# charger.net
KiCad netlist of a schematic drawn in Altium Designer
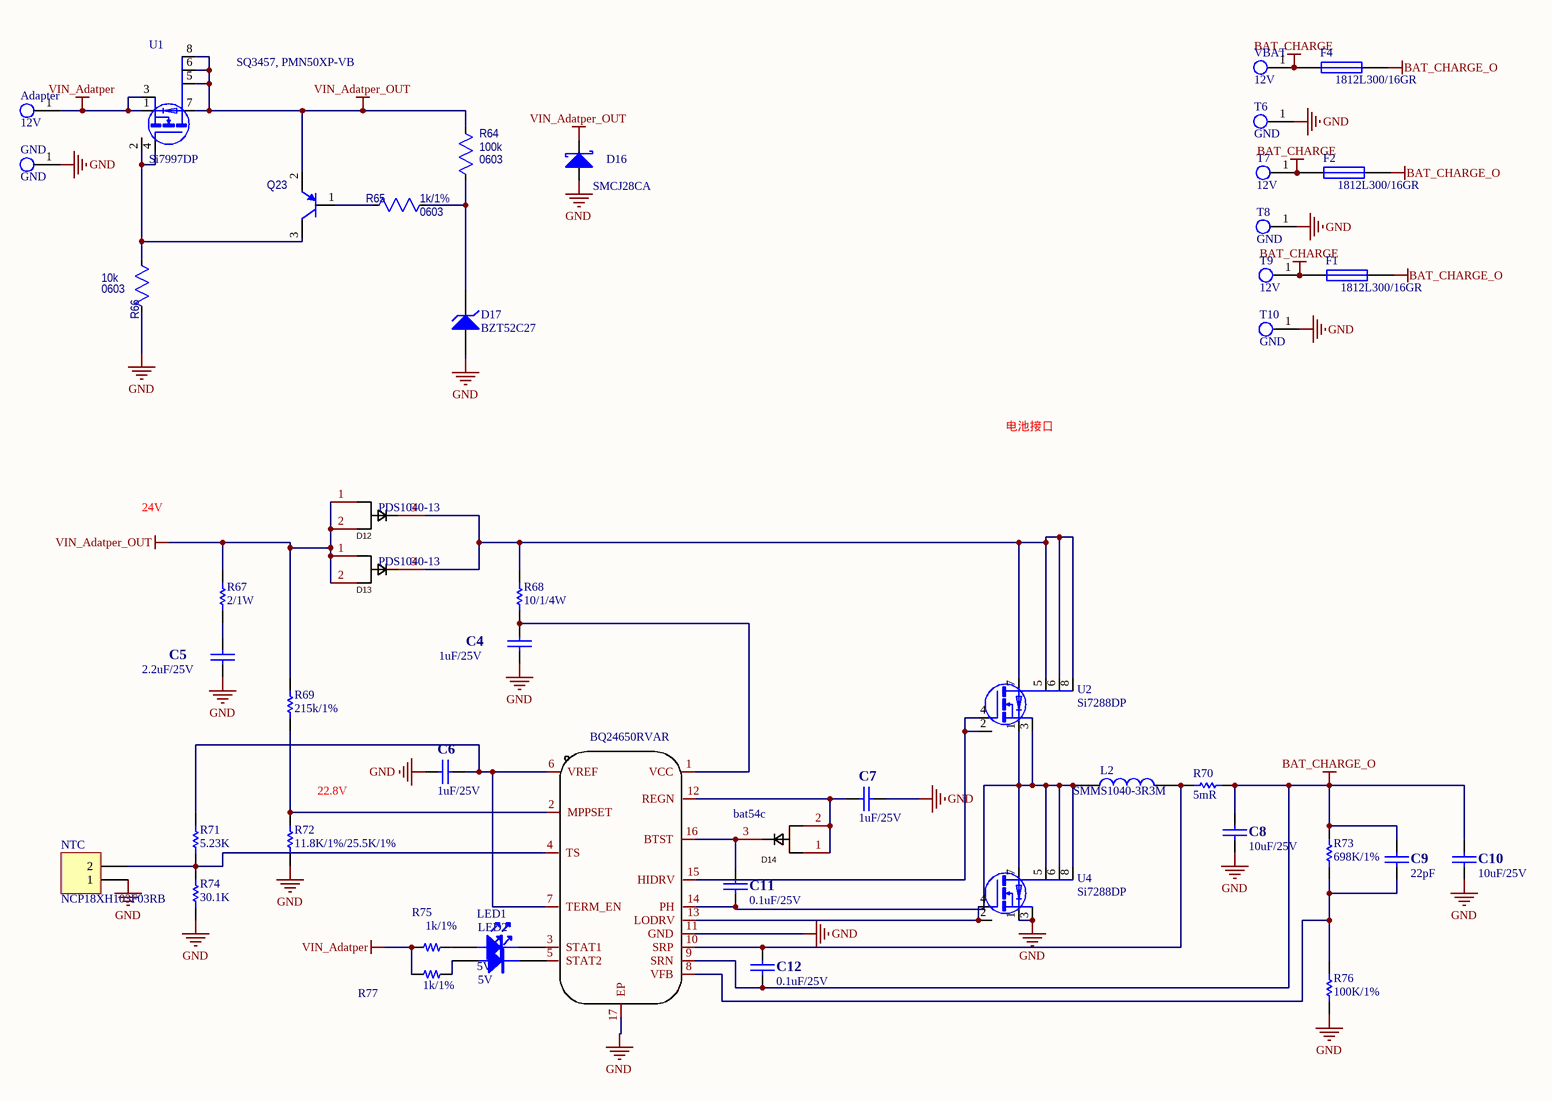
[diagram p0: charger.SchDoc]

(export (version "E")
  (design (tool "Eeschema 10.0.6"))
  (components
    (comp (ref "Adapter") (value "12V") (footprint "FIX-4.5") (libsource (lib "Schlib_20110825") (part "TP")))
    (comp (ref "C4")
      (value "1uF/25V")
      (footprint "0805C")
      (description "Capacitor")
      (libsource (lib "*") (part "CAP"))
    )
    (comp (ref "C5")
      (value "2.2uF/25V")
      (footprint "1210C")
      (description "Capacitor")
      (libsource (lib "*") (part "CAP"))
    )
    (comp (ref "C6")
      (value "1uF/25V")
      (footprint "0603C")
      (description "Capacitor")
      (libsource (lib "*") (part "CAP"))
    )
    (comp (ref "C7")
      (value "1uF/25V")
      (footprint "0603C")
      (description "Capacitor")
      (libsource (lib "*") (part "CAP"))
    )
    (comp (ref "C8")
      (value "10uF/25V")
      (footprint "0603C")
      (description "Capacitor")
      (libsource (lib "*") (part "CAP"))
    )
    (comp (ref "C9")
      (value "22pF")
      (footprint "0603C")
      (description "Capacitor")
      (libsource (lib "*") (part "CAP"))
    )
    (comp (ref "C10")
      (value "10uF/25V")
      (footprint "0603C")
      (description "Capacitor")
      (libsource (lib "*") (part "CAP"))
    )
    (comp (ref "C11")
      (value "0.1uF/25V")
      (footprint "0603C")
      (description "Capacitor")
      (libsource (lib "*") (part "CAP"))
    )
    (comp (ref "C12")
      (value "0.1uF/25V")
      (footprint "0603C")
      (description "Capacitor")
      (libsource (lib "*") (part "CAP"))
    )
    (comp (ref "D12")
      (value "PDS1040-13")
      (footprint "POWERDI-5_L5.4-W4.0-LS6.5-RD")
      (fields (field (name "MANUFACTURER") "DIODES(美台)"))
      (libsource (lib "Schlib_20110825") (part "PDS1040-13"))
    )
    (comp (ref "D13")
      (value "PDS1040-13")
      (footprint "POWERDI-5_L5.4-W4.0-LS6.5-RD")
      (fields (field (name "MANUFACTURER") "DIODES(美台)"))
      (libsource (lib "Schlib_20110825") (part "PDS1040-13"))
    )
    (comp (ref "D14")
      (value "bat54c")
      (footprint "sot23-3")
      (fields (field (name "MANUFACTURER") "DIODES(美台)") (field (name "MANUFACTURER PART") "PDS1040-13"))
      (libsource (lib "Schlib_20110825") (part "PDS1040-13"))
    )
    (comp (ref "D16")
      (value "SMCJ28CA")
      (footprint "SMC")
      (description "Schottky Diode")
      (libsource (lib "*") (part "DIODE S"))
    )
    (comp (ref "D17")
      (value "BZT52C27")
      (footprint "sod123")
      (libsource (lib "Bogen") (part "BZT52C12S-7-F"))
    )
    (comp (ref "F1")
      (value "1812L300/16GR")
      (footprint "1812-F")
      (description "Fuse")
      (fields (field (name "PUBLISHER") "Altium Limited"))
      (libsource (lib "Miscellaneous Devices") (part "Fuse 1"))
    )
    (comp (ref "F2")
      (value "1812L300/16GR")
      (footprint "1812-F")
      (description "Fuse")
      (fields (field (name "PUBLISHER") "Altium Limited"))
      (libsource (lib "Miscellaneous Devices") (part "Fuse 1"))
    )
    (comp (ref "F4")
      (value "1812L300/16GR")
      (footprint "1812-F")
      (description "Fuse")
      (fields (field (name "PUBLISHER") "Altium Limited"))
      (libsource (lib "Miscellaneous Devices") (part "Fuse 1"))
    )
    (comp (ref "GND") (value "GND") (footprint "FIX-4.5") (libsource (lib "Schlib_20110825") (part "TP")))
    (comp (ref "L2") (value "SMMS1040-3R3M") (footprint "MSS1038") (libsource (lib "*") (part "INDUCTOR")))
    (comp (ref "LED1") (value "5V") (footprint "0603LED") (libsource (lib "*") (part "LED")))
    (comp (ref "LED2") (value "5V") (footprint "0603LED") (libsource (lib "*") (part "LED")))
    (comp (ref "NTC")
      (value "NCP18XH103F03RB")
      (footprint "HDR1X2")
      (description "XH2.54 2P 立贴")
      (fields (field (name "PUBLISHER") "Altium Limited"))
      (libsource (lib "Miscellaneous Connectors") (part "Header 2"))
    )
    (comp (ref "Q23")
      (value "MMBT4403-7-F")
      (footprint "SOT23-3")
      (libsource (lib "Karl") (part "OEM_Diodes_MMBT4403"))
    )
    (comp (ref "R64")
      (value "100k")
      (footprint "RESC1608X055N_0603")
      (fields
        (field (name "PARTNUMBER") "RC0603FR-0716K9L")
        (field (name "TOLERANCE") "tol")
        (field (name "PACKAGE") "0603")
      )
      (libsource (lib "Karl") (part "Resistor_0603"))
    )
    (comp (ref "R65")
      (value "1k/1%")
      (footprint "RESC1608X055N_0603")
      (fields
        (field (name "PARTNUMBER") "RC0603FR-071KL")
        (field (name "TOLERANCE") "tol")
        (field (name "PACKAGE") "0603")
      )
      (libsource (lib "Karl") (part "Resistor_0603"))
    )
    (comp (ref "R66")
      (value "10k")
      (footprint "RESC1608X055N_0603")
      (fields
        (field (name "PARTNUMBER") "RC0603FR-071KL")
        (field (name "TOLERANCE") "tol")
        (field (name "PACKAGE") "0603")
      )
      (libsource (lib "Karl") (part "Resistor_0603"))
    )
    (comp (ref "R67")
      (value "2/1W")
      (footprint "2512R")
      (description "Resistor")
      (fields (field (name "PUBLISHER") "Altium Limited"))
      (libsource (lib "Miscellaneous Devices") (part "Res1"))
    )
    (comp (ref "R68")
      (value "10/1/4W")
      (footprint "1206R")
      (description "Resistor")
      (fields (field (name "PUBLISHER") "Altium Limited"))
      (libsource (lib "Miscellaneous Devices") (part "Res1"))
    )
    (comp (ref "R69")
      (value "215k/1%")
      (footprint "0603R")
      (description "Resistor")
      (fields (field (name "PUBLISHER") "Altium Limited"))
      (libsource (lib "Miscellaneous Devices") (part "Res1"))
    )
    (comp (ref "R70")
      (value "5mR")
      (footprint "2512R")
      (description "Resistor")
      (fields (field (name "PUBLISHER") "Altium Limited"))
      (libsource (lib "Miscellaneous Devices") (part "Res1"))
    )
    (comp (ref "R71")
      (value "5.23K")
      (footprint "0603R")
      (description "Resistor")
      (fields (field (name "PUBLISHER") "Altium Limited"))
      (libsource (lib "Miscellaneous Devices") (part "Res1"))
    )
    (comp (ref "R72")
      (value "11.8K/1%/25.5K/1%")
      (footprint "0603R")
      (description "Resistor")
      (fields (field (name "PUBLISHER") "Altium Limited"))
      (libsource (lib "Miscellaneous Devices") (part "Res1"))
    )
    (comp (ref "R73")
      (value "698K/1%")
      (footprint "0603R")
      (description "Resistor")
      (fields (field (name "PUBLISHER") "Altium Limited"))
      (libsource (lib "Miscellaneous Devices") (part "Res1"))
    )
    (comp (ref "R74")
      (value "30.1K")
      (footprint "0603R")
      (description "Resistor")
      (fields (field (name "PUBLISHER") "Altium Limited"))
      (libsource (lib "Miscellaneous Devices") (part "Res1"))
    )
    (comp (ref "R75") (value "1k/1%") (footprint "0603R") (libsource (lib "JRJ_1") (part "R")))
    (comp (ref "R76")
      (value "100K/1%")
      (footprint "0603R")
      (description "Resistor")
      (fields (field (name "PUBLISHER") "Altium Limited"))
      (libsource (lib "Miscellaneous Devices") (part "Res1"))
    )
    (comp (ref "R77") (value "1k/1%") (footprint "0603R") (libsource (lib "JRJ_1") (part "R")))
    (comp (ref "T6") (value "GND") (footprint "FIX-4.5") (libsource (lib "Schlib_20110825") (part "TP")))
    (comp (ref "T7") (value "12V") (footprint "FIX-4.5") (libsource (lib "Schlib_20110825") (part "TP")))
    (comp (ref "T8") (value "GND") (footprint "FIX-4.5") (libsource (lib "Schlib_20110825") (part "TP")))
    (comp (ref "T9") (value "12V") (footprint "FIX-4.5") (libsource (lib "Schlib_20110825") (part "TP")))
    (comp (ref "T10") (value "GND") (footprint "FIX-4.5") (libsource (lib "Schlib_20110825") (part "TP")))
    (comp (ref "U1")
      (value "Si7997DP")
      (footprint "PowerPAK SO-8")
      (description "Sia430DJ")
      (libsource (lib "Schlib_20110825") (part "Si7997DP"))
    )
    (comp (ref "U2")
      (value "Si7288DP")
      (footprint "PowerPAK SO-8")
      (description "Sia430DJ")
      (libsource (lib "Schlib_20110825") (part "Si7997DP"))
    )
    (comp (ref "U4")
      (value "Si7288DP")
      (footprint "PowerPAK SO-8")
      (description "Sia430DJ")
      (libsource (lib "Schlib_20110825") (part "Si7997DP"))
    )
    (comp (ref "U5")
      (value "BQ24650RVAR")
      (footprint "VQFN-16_L3.6-W3.6-P0.50-BL-EP")
      (fields (field (name "MANUFACTURER") "TI(德州仪器)"))
      (libsource (lib "Schlib_20110825") (part "BQ24650RVAR"))
    )
    (comp (ref "VBAT") (value "12V") (footprint "FIX-4.5") (libsource (lib "Schlib_20110825") (part "TP")))
  )
  (nets
    (net (code "1") (name "BAT_CHARGE") (class "Default")
      (node (ref "F1") (pin "1") (pinfunction "1_1") (pintype "passive"))
      (node (ref "F2") (pin "1") (pinfunction "1_1") (pintype "passive"))
      (node (ref "F4") (pin "1") (pinfunction "1_1") (pintype "passive"))
      (node (ref "T7") (pin "1") (pintype "passive"))
      (node (ref "T9") (pin "1") (pintype "passive"))
      (node (ref "VBAT") (pin "1") (pintype "passive"))
    )
    (net (code "2") (name "BAT_CHARGE_O") (class "Default")
      (node (ref "C10") (pin "2") (pinfunction "2_2") (pintype "passive"))
      (node (ref "C12") (pin "1") (pinfunction "1_1") (pintype "passive"))
      (node (ref "C8") (pin "2") (pinfunction "2_2") (pintype "passive"))
      (node (ref "C9") (pin "2") (pinfunction "2_2") (pintype "passive"))
      (node (ref "F1") (pin "2") (pinfunction "2_2") (pintype "passive"))
      (node (ref "F2") (pin "2") (pinfunction "2_2") (pintype "passive"))
      (node (ref "F4") (pin "2") (pinfunction "2_2") (pintype "passive"))
      (node (ref "R70") (pin "2") (pinfunction "2_2") (pintype "passive"))
      (node (ref "R73") (pin "1") (pinfunction "1_1") (pintype "passive"))
      (node (ref "U5") (pin "9") (pinfunction "SRN_9") (pintype "passive"))
    )
    (net (code "3") (name "GND") (class "Default")
      (node (ref "C10") (pin "1") (pinfunction "1_1") (pintype "passive"))
      (node (ref "C4") (pin "2") (pinfunction "2_2") (pintype "passive"))
      (node (ref "C5") (pin "2") (pinfunction "2_2") (pintype "passive"))
      (node (ref "C6") (pin "1") (pinfunction "1_1") (pintype "passive"))
      (node (ref "C7") (pin "2") (pinfunction "2_2") (pintype "passive"))
      (node (ref "C8") (pin "1") (pinfunction "1_1") (pintype "passive"))
      (node (ref "D16") (pin "1") (pinfunction "A_1") (pintype "passive"))
      (node (ref "D17") (pin "1") (pinfunction "A_1") (pintype "passive"))
      (node (ref "GND") (pin "1") (pintype "passive"))
      (node (ref "NTC") (pin "1") (pinfunction "1_1") (pintype "passive"))
      (node (ref "R66") (pin "2") (pinfunction "2_2") (pintype "passive"))
      (node (ref "R72") (pin "2") (pinfunction "2_2") (pintype "passive"))
      (node (ref "R74") (pin "2") (pinfunction "2_2") (pintype "passive"))
      (node (ref "R76") (pin "2") (pinfunction "2_2") (pintype "passive"))
      (node (ref "T10") (pin "1") (pintype "passive"))
      (node (ref "T6") (pin "1") (pintype "passive"))
      (node (ref "T8") (pin "1") (pintype "passive"))
      (node (ref "U4") (pin "1") (pinfunction "S_1") (pintype "passive"))
      (node (ref "U4") (pin "3") (pinfunction "S_3") (pintype "passive"))
      (node (ref "U5") (pin "11") (pinfunction "GND_11") (pintype "passive"))
      (node (ref "U5") (pin "17") (pinfunction "EP_17") (pintype "passive"))
    )
    (net (code "4") (name "Net-(C5-Pad1)") (class "Default")
      (node (ref "C5") (pin "1") (pinfunction "1_1") (pintype "passive"))
      (node (ref "R67") (pin "2") (pinfunction "2_2") (pintype "passive"))
    )
    (net (code "5") (name "Net-(D12-Pad3)") (class "Default")
      (node (ref "D12") (pin "3") (pinfunction "3_3") (pintype "passive"))
      (node (ref "D13") (pin "3") (pinfunction "3_3") (pintype "passive"))
      (node (ref "R68") (pin "1") (pinfunction "1_1") (pintype "passive"))
      (node (ref "U2") (pin "5") (pinfunction "D_5") (pintype "passive"))
      (node (ref "U2") (pin "6") (pinfunction "D_6") (pintype "passive"))
      (node (ref "U2") (pin "7") (pinfunction "D_7") (pintype "passive"))
      (node (ref "U2") (pin "8") (pinfunction "D_8") (pintype "passive"))
    )
    (net (code "6") (name "Net-(D14-LEFT)") (class "Default")
      (node (ref "C7") (pin "1") (pinfunction "1_1") (pintype "passive"))
      (node (ref "D14") (pin "1") (pinfunction "LEFT_1") (pintype "passive"))
      (node (ref "D14") (pin "2") (pinfunction "RIGHT_2") (pintype "passive"))
      (node (ref "U5") (pin "12") (pinfunction "REGN_12") (pintype "passive"))
    )
    (net (code "7") (name "Net-(D17-K)") (class "Default")
      (node (ref "D17") (pin "2") (pinfunction "K_2") (pintype "passive"))
      (node (ref "R64") (pin "1") (pinfunction "1_1") (pintype "passive"))
      (node (ref "R65") (pin "1") (pinfunction "1_1") (pintype "passive"))
    )
    (net (code "8") (name "Net-(LED1-Pad1)") (class "Default")
      (node (ref "LED1") (pin "1") (pinfunction "1_1") (pintype "passive"))
      (node (ref "R75") (pin "1") (pintype "passive"))
    )
    (net (code "9") (name "Net-(LED2-Pad1)") (class "Default")
      (node (ref "LED2") (pin "1") (pinfunction "1_1") (pintype "passive"))
      (node (ref "R77") (pin "1") (pintype "passive"))
    )
    (net (code "10") (name "Net-(Q23-B)") (class "Default")
      (node (ref "Q23") (pin "1") (pinfunction "B_1") (pintype "passive"))
      (node (ref "R65") (pin "2") (pinfunction "2_2") (pintype "passive"))
    )
    (net (code "11") (name "Net-(Q23-C)") (class "Default")
      (node (ref "Q23") (pin "3") (pinfunction "C_3") (pintype "passive"))
      (node (ref "R66") (pin "1") (pinfunction "1_1") (pintype "passive"))
      (node (ref "U1") (pin "2") (pinfunction "G_2") (pintype "passive"))
      (node (ref "U1") (pin "4") (pinfunction "G_4") (pintype "passive"))
    )
    (net (code "12") (name "Net-(U5-BTST)") (class "Default")
      (node (ref "C11") (pin "2") (pinfunction "2_2") (pintype "passive"))
      (node (ref "D14") (pin "3") (pinfunction "3_3") (pintype "passive"))
      (node (ref "U5") (pin "16") (pinfunction "BTST_16") (pintype "passive"))
    )
    (net (code "13") (name "Net-(U5-HIDRV)") (class "Default")
      (node (ref "U2") (pin "2") (pinfunction "G_2") (pintype "passive"))
      (node (ref "U2") (pin "4") (pinfunction "G_4") (pintype "passive"))
      (node (ref "U5") (pin "15") (pinfunction "HIDRV_15") (pintype "passive"))
    )
    (net (code "14") (name "Net-(U5-LODRV)") (class "Default")
      (node (ref "U4") (pin "2") (pinfunction "G_2") (pintype "passive"))
      (node (ref "U4") (pin "4") (pinfunction "G_4") (pintype "passive"))
      (node (ref "U5") (pin "13") (pinfunction "LODRV_13") (pintype "passive"))
    )
    (net (code "15") (name "Net-(U5-MPPSET)") (class "Default")
      (node (ref "R69") (pin "2") (pinfunction "2_2") (pintype "passive"))
      (node (ref "R72") (pin "1") (pinfunction "1_1") (pintype "passive"))
      (node (ref "U5") (pin "2") (pinfunction "MPPSET_2") (pintype "passive"))
    )
    (net (code "16") (name "Net-(U5-PH)") (class "Default")
      (node (ref "C11") (pin "1") (pinfunction "1_1") (pintype "passive"))
      (node (ref "L2") (pin "1") (pinfunction "1_1") (pintype "passive"))
      (node (ref "U2") (pin "1") (pinfunction "S_1") (pintype "passive"))
      (node (ref "U2") (pin "3") (pinfunction "S_3") (pintype "passive"))
      (node (ref "U4") (pin "5") (pinfunction "D_5") (pintype "passive"))
      (node (ref "U4") (pin "6") (pinfunction "D_6") (pintype "passive"))
      (node (ref "U4") (pin "7") (pinfunction "D_7") (pintype "passive"))
      (node (ref "U4") (pin "8") (pinfunction "D_8") (pintype "passive"))
      (node (ref "U5") (pin "14") (pinfunction "PH_14") (pintype "passive"))
    )
    (net (code "17") (name "Net-(U5-SRP)") (class "Default")
      (node (ref "C12") (pin "2") (pinfunction "2_2") (pintype "passive"))
      (node (ref "L2") (pin "2") (pinfunction "2_2") (pintype "passive"))
      (node (ref "R70") (pin "1") (pinfunction "1_1") (pintype "passive"))
      (node (ref "U5") (pin "10") (pinfunction "SRP_10") (pintype "passive"))
    )
    (net (code "18") (name "Net-(U5-STAT1)") (class "Default")
      (node (ref "LED1") (pin "2") (pinfunction "2_2") (pintype "passive"))
      (node (ref "U5") (pin "3") (pinfunction "STAT1_3") (pintype "passive"))
    )
    (net (code "19") (name "Net-(U5-TERM_EN)") (class "Default")
      (node (ref "C6") (pin "2") (pinfunction "2_2") (pintype "passive"))
      (node (ref "R71") (pin "1") (pinfunction "1_1") (pintype "passive"))
      (node (ref "U5") (pin "6") (pinfunction "VREF_6") (pintype "passive"))
      (node (ref "U5") (pin "7") (pinfunction "TERM_EN_7") (pintype "passive"))
    )
    (net (code "20") (name "Net-(U5-TS)") (class "Default")
      (node (ref "NTC") (pin "2") (pinfunction "2_2") (pintype "passive"))
      (node (ref "R71") (pin "2") (pinfunction "2_2") (pintype "passive"))
      (node (ref "R74") (pin "1") (pinfunction "1_1") (pintype "passive"))
      (node (ref "U5") (pin "4") (pinfunction "TS_4") (pintype "passive"))
    )
    (net (code "21") (name "Net-(U5-VCC)") (class "Default")
      (node (ref "C4") (pin "1") (pinfunction "1_1") (pintype "passive"))
      (node (ref "R68") (pin "2") (pinfunction "2_2") (pintype "passive"))
      (node (ref "U5") (pin "1") (pinfunction "VCC_1") (pintype "passive"))
    )
    (net (code "22") (name "Net-(U5-VFB)") (class "Default")
      (node (ref "C9") (pin "1") (pinfunction "1_1") (pintype "passive"))
      (node (ref "R73") (pin "2") (pinfunction "2_2") (pintype "passive"))
      (node (ref "R76") (pin "1") (pinfunction "1_1") (pintype "passive"))
      (node (ref "U5") (pin "8") (pinfunction "VFB_8") (pintype "passive"))
    )
    (net (code "23") (name "VIN_Adatper") (class "Default")
      (node (ref "Adapter") (pin "1") (pintype "passive"))
      (node (ref "R75") (pin "2") (pintype "passive"))
      (node (ref "R77") (pin "2") (pintype "passive"))
      (node (ref "U1") (pin "1") (pinfunction "S_1") (pintype "passive"))
      (node (ref "U1") (pin "3") (pinfunction "S_3") (pintype "passive"))
    )
    (net (code "24") (name "VIN_Adatper_OUT") (class "Default")
      (node (ref "D12") (pin "1") (pinfunction "LEFT_1") (pintype "passive"))
      (node (ref "D12") (pin "2") (pinfunction "RIGHT_2") (pintype "passive"))
      (node (ref "D13") (pin "1") (pinfunction "LEFT_1") (pintype "passive"))
      (node (ref "D13") (pin "2") (pinfunction "RIGHT_2") (pintype "passive"))
      (node (ref "D16") (pin "2") (pinfunction "K_2") (pintype "passive"))
      (node (ref "Q23") (pin "2") (pinfunction "E_2") (pintype "passive"))
      (node (ref "R64") (pin "2") (pinfunction "2_2") (pintype "passive"))
      (node (ref "R67") (pin "1") (pinfunction "1_1") (pintype "passive"))
      (node (ref "R69") (pin "1") (pinfunction "1_1") (pintype "passive"))
      (node (ref "U1") (pin "5") (pinfunction "D_5") (pintype "passive"))
      (node (ref "U1") (pin "6") (pinfunction "D_6") (pintype "passive"))
      (node (ref "U1") (pin "7") (pinfunction "D_7") (pintype "passive"))
      (node (ref "U1") (pin "8") (pinfunction "D_8") (pintype "passive"))
    )
    (net (code "25") (name "unconnected-(LED2-Pad2)") (class "Default")
      (node (ref "LED2") (pin "2") (pinfunction "2_2") (pintype "passive"))
    )
    (net (code "26") (name "unconnected-(U5-STAT2-Pad5)") (class "Default")
      (node (ref "U5") (pin "5") (pinfunction "STAT2_5") (pintype "passive"))
    )
  )
)
